# RADC-Peripherals-S06-V00.net
KiCad netlist of a schematic drawn in Altium Designer
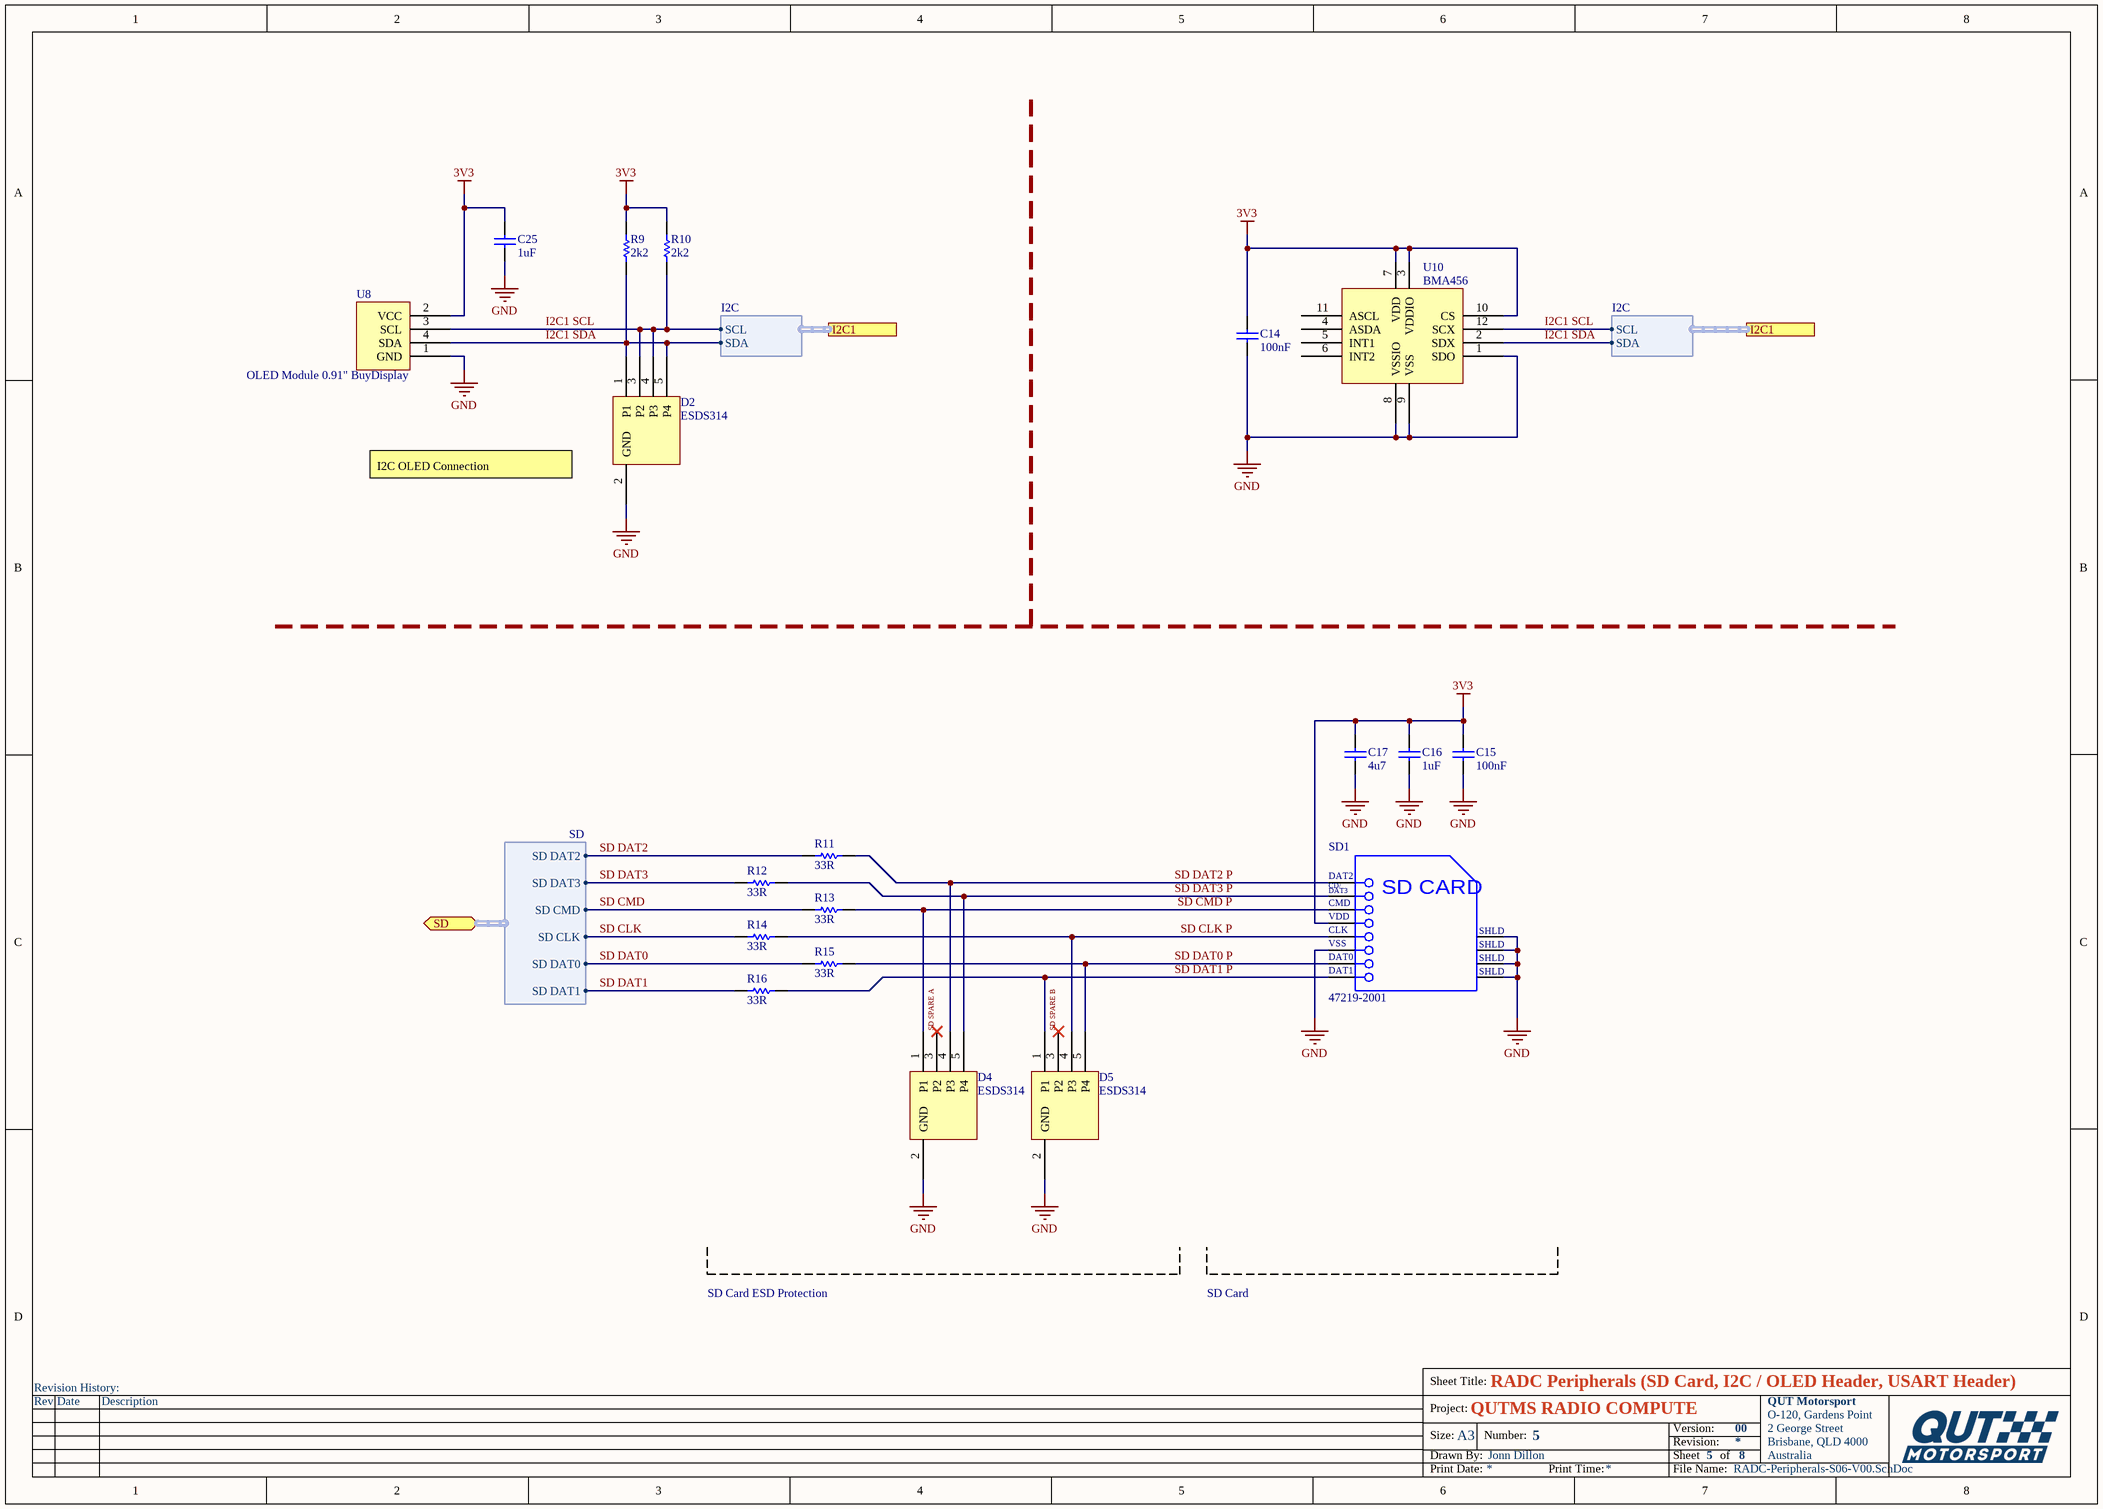
[diagram p0: RADC-Peripherals-S06-V00.SchDoc]

(export (version "E")
  (design (tool "Eeschema 10.0.6"))
  (components
    (comp (ref "C14")
      (value "100nF")
      (footprint "Cap_Ceramic_0603")
      (description "Capacitor, Ceramic, SMD, 100nF, 50V, 5%, X7R, 0603")
      (libsource (lib "StandardCapacitors") (part "100nF 50V 5% X7R 0603"))
    )
    (comp (ref "C15")
      (value "100nF")
      (footprint "Cap_Ceramic_0603")
      (description "Capacitor, Ceramic, SMD, 100nF, 50V, 5%, X7R, 0603")
      (libsource (lib "StandardCapacitors") (part "100nF 50V 5% X7R 0603"))
    )
    (comp (ref "C16")
      (value "1uF")
      (footprint "Cap_Ceramic_0603")
      (description "Capacitor, Ceramic, SMD, 1uF, 25V, 5%, X7R, 0603")
      (libsource (lib "StandardCapacitors") (part "1uF 25V 5% X7R 0603"))
    )
    (comp (ref "C17")
      (value "4u7")
      (footprint "Cap_Ceramic_0603")
      (description "Capacitor, Ceramic, SMD, 4u7, 50V, 5%, X7R, 0603")
      (libsource (lib "StandardCapacitors") (part "4u7 50V 5% X7R 0603"))
    )
    (comp (ref "C25")
      (value "1uF")
      (footprint "Cap_Ceramic_0603")
      (description "Capacitor, Ceramic, SMD, 1uF, 25V, 5%, X7R, 0603")
      (libsource (lib "StandardCapacitors") (part "1uF 25V 5% X7R 0603"))
    )
    (comp (ref "D2")
      (value "ESDS314")
      (footprint "SOT-23-5")
      (description "6.5V (Typ) Clamp 25A (8/20µs) Ipp Tvs Diode Surface Mount SOT-23-5")
      (libsource (lib "QUTMS_DiodeLibrary") (part "ESDS314"))
    )
    (comp (ref "D4")
      (value "ESDS314")
      (footprint "SOT-23-5")
      (description "6.5V (Typ) Clamp 25A (8/20µs) Ipp Tvs Diode Surface Mount SOT-23-5")
      (libsource (lib "QUTMS_DiodeLibrary") (part "ESDS314"))
    )
    (comp (ref "D5")
      (value "ESDS314")
      (footprint "SOT-23-5")
      (description "6.5V (Typ) Clamp 25A (8/20µs) Ipp Tvs Diode Surface Mount SOT-23-5")
      (libsource (lib "QUTMS_DiodeLibrary") (part "ESDS314"))
    )
    (comp (ref "R9")
      (value "2k2")
      (footprint "Res_ThinFilm_0603")
      (description "Resistor, SMD, 2k2, 0.1W, 5%, 0603")
      (libsource (lib "StandardResistors") (part "2k2 5% 0603"))
    )
    (comp (ref "R10")
      (value "2k2")
      (footprint "Res_ThinFilm_0603")
      (description "Resistor, SMD, 2k2, 0.1W, 5%, 0603")
      (libsource (lib "StandardResistors") (part "2k2 5% 0603"))
    )
    (comp (ref "R11")
      (value "33R")
      (footprint "Res_ThinFilm_0603")
      (description "Resistor, SMD, 33R, 0.1W, 5%, 0603")
      (libsource (lib "StandardResistors") (part "33R 5% 0603"))
    )
    (comp (ref "R12")
      (value "33R")
      (footprint "Res_ThinFilm_0603")
      (description "Resistor, SMD, 33R, 0.1W, 5%, 0603")
      (libsource (lib "StandardResistors") (part "33R 5% 0603"))
    )
    (comp (ref "R13")
      (value "33R")
      (footprint "Res_ThinFilm_0603")
      (description "Resistor, SMD, 33R, 0.1W, 5%, 0603")
      (libsource (lib "StandardResistors") (part "33R 5% 0603"))
    )
    (comp (ref "R14")
      (value "33R")
      (footprint "Res_ThinFilm_0603")
      (description "Resistor, SMD, 33R, 0.1W, 5%, 0603")
      (libsource (lib "StandardResistors") (part "33R 5% 0603"))
    )
    (comp (ref "R15")
      (value "33R")
      (footprint "Res_ThinFilm_0603")
      (description "Resistor, SMD, 33R, 0.1W, 5%, 0603")
      (libsource (lib "StandardResistors") (part "33R 5% 0603"))
    )
    (comp (ref "R16")
      (value "33R")
      (footprint "Res_ThinFilm_0603")
      (description "Resistor, SMD, 33R, 0.1W, 5%, 0603")
      (libsource (lib "StandardResistors") (part "33R 5% 0603"))
    )
    (comp (ref "SD1")
      (value "47219-2001")
      (footprint "47219-2001")
      (description "MicroSD Card Connector, Hinge Type, -40 to 85 degC, 8-Pin SMD, RoHS, Tape and Reel")
      (libsource (lib "QUTMS_PeripheralConnectivity") (part "47219-2001"))
    )
    (comp (ref "U8")
      (value "OLED Module 0.91\" BuyDisplay")
      (footprint "BuyDisplay 0.91\" OLED")
      (description "I2C Blue 0.91\" inch OLED Display Module 128x32 Arduino,Raspberry Pi")
      (libsource (lib "QUTMS_IntegratedCircuitLibrary") (part "OLED Module 0.91{dblquote} BuyDisplay"))
    )
    (comp (ref "U10")
      (value "BMA456")
      (footprint "BMA456")
      (description "Accelerometer X, Y, Z Axis ±2g, 4g, 8g, 16g 1.5kHz ~ 1.6kHz 12-LGA (2x2)")
      (libsource (lib "QUTMS_IntegratedCircuitLibrary") (part "BMA456"))
    )
  )
  (nets
    (net (code "3") (name "/I2C1 SCL") (class "Default")
      (node (ref "D2") (pin "3") (pinfunction "P2_3") (pintype "passive"))
      (node (ref "D2") (pin "4") (pinfunction "P3_4") (pintype "passive"))
      (node (ref "R10") (pin "1") (pinfunction "1_1") (pintype "passive"))
      (node (ref "U10") (pin "12") (pinfunction "SCX_12") (pintype "passive"))
      (node (ref "U8") (pin "3") (pinfunction "SCL_3") (pintype "passive"))
    )
    (net (code "4") (name "/I2C1 SDA") (class "Default")
      (node (ref "D2") (pin "1") (pinfunction "P1_1") (pintype "passive"))
      (node (ref "D2") (pin "5") (pinfunction "P4_5") (pintype "passive"))
      (node (ref "R9") (pin "1") (pinfunction "1_1") (pintype "passive"))
      (node (ref "U10") (pin "2") (pinfunction "SDX_2") (pintype "passive"))
      (node (ref "U8") (pin "4") (pinfunction "SDA_4") (pintype "passive"))
    )
    (net (code "5") (name "/SD CLK") (class "Default")
      (node (ref "R14") (pin "1") (pinfunction "1_1") (pintype "passive"))
    )
    (net (code "6") (name "/SD CLK P") (class "Default")
      (node (ref "D5") (pin "4") (pinfunction "P3_4") (pintype "passive"))
      (node (ref "R14") (pin "2") (pinfunction "2_2") (pintype "passive"))
      (node (ref "SD1") (pin "5") (pinfunction "CLK_5") (pintype "passive"))
    )
    (net (code "7") (name "/SD CMD") (class "Default")
      (node (ref "R13") (pin "1") (pinfunction "1_1") (pintype "passive"))
    )
    (net (code "8") (name "/SD CMD P") (class "Default")
      (node (ref "D4") (pin "1") (pinfunction "P1_1") (pintype "passive"))
      (node (ref "R13") (pin "2") (pinfunction "2_2") (pintype "passive"))
      (node (ref "SD1") (pin "3") (pinfunction "CMD_3") (pintype "passive"))
    )
    (net (code "9") (name "/SD DAT0") (class "Default")
      (node (ref "R15") (pin "1") (pinfunction "1_1") (pintype "passive"))
    )
    (net (code "10") (name "/SD DAT0 P") (class "Default")
      (node (ref "D5") (pin "5") (pinfunction "P4_5") (pintype "passive"))
      (node (ref "R15") (pin "2") (pinfunction "2_2") (pintype "passive"))
      (node (ref "SD1") (pin "7") (pinfunction "DAT0_7") (pintype "passive"))
    )
    (net (code "11") (name "/SD DAT1") (class "Default")
      (node (ref "R16") (pin "1") (pinfunction "1_1") (pintype "passive"))
    )
    (net (code "12") (name "/SD DAT1 P") (class "Default")
      (node (ref "D5") (pin "1") (pinfunction "P1_1") (pintype "passive"))
      (node (ref "R16") (pin "2") (pinfunction "2_2") (pintype "passive"))
      (node (ref "SD1") (pin "8") (pinfunction "DAT1_8") (pintype "passive"))
    )
    (net (code "13") (name "/SD DAT2") (class "Default")
      (node (ref "R11") (pin "1") (pinfunction "1_1") (pintype "passive"))
    )
    (net (code "14") (name "/SD DAT2 P") (class "Default")
      (node (ref "D4") (pin "4") (pinfunction "P3_4") (pintype "passive"))
      (node (ref "R11") (pin "2") (pinfunction "2_2") (pintype "passive"))
      (node (ref "SD1") (pin "1") (pinfunction "DAT2_1") (pintype "passive"))
    )
    (net (code "15") (name "/SD DAT3") (class "Default")
      (node (ref "R12") (pin "1") (pinfunction "1_1") (pintype "passive"))
    )
    (net (code "16") (name "/SD DAT3 P") (class "Default")
      (node (ref "D4") (pin "5") (pinfunction "P4_5") (pintype "passive"))
      (node (ref "R12") (pin "2") (pinfunction "2_2") (pintype "passive"))
      (node (ref "SD1") (pin "2") (pinfunction "CD/DAT3_2") (pintype "passive"))
    )
    (net (code "17") (name "/SD SPARE A") (class "Default")
      (node (ref "D4") (pin "3") (pinfunction "P2_3") (pintype "passive+no_connect"))
    )
    (net (code "18") (name "/SD SPARE B") (class "Default")
      (node (ref "D5") (pin "3") (pinfunction "P2_3") (pintype "passive+no_connect"))
    )
    (net (code "21") (name "3V3") (class "Default")
      (node (ref "C14") (pin "2") (pinfunction "2_2") (pintype "passive"))
      (node (ref "C15") (pin "2") (pinfunction "2_2") (pintype "passive"))
      (node (ref "C16") (pin "2") (pinfunction "2_2") (pintype "passive"))
      (node (ref "C17") (pin "2") (pinfunction "2_2") (pintype "passive"))
      (node (ref "C25") (pin "2") (pinfunction "2_2") (pintype "passive"))
      (node (ref "R10") (pin "2") (pinfunction "2_2") (pintype "passive"))
      (node (ref "R9") (pin "2") (pinfunction "2_2") (pintype "passive"))
      (node (ref "SD1") (pin "4") (pinfunction "VDD_4") (pintype "passive"))
      (node (ref "U10") (pin "10") (pinfunction "CS_10") (pintype "passive"))
      (node (ref "U10") (pin "3") (pinfunction "VDDIO_3") (pintype "passive"))
      (node (ref "U10") (pin "7") (pinfunction "VDD_7") (pintype "passive"))
      (node (ref "U8") (pin "2") (pinfunction "VCC_2") (pintype "passive"))
    )
    (net (code "22") (name "GND") (class "Default")
      (node (ref "C14") (pin "1") (pinfunction "1_1") (pintype "passive"))
      (node (ref "C15") (pin "1") (pinfunction "1_1") (pintype "passive"))
      (node (ref "C16") (pin "1") (pinfunction "1_1") (pintype "passive"))
      (node (ref "C17") (pin "1") (pinfunction "1_1") (pintype "passive"))
      (node (ref "C25") (pin "1") (pinfunction "1_1") (pintype "passive"))
      (node (ref "D2") (pin "2") (pinfunction "GND_2") (pintype "passive"))
      (node (ref "D4") (pin "2") (pinfunction "GND_2") (pintype "passive"))
      (node (ref "D5") (pin "2") (pinfunction "GND_2") (pintype "passive"))
      (node (ref "SD1") (pin "10") (pinfunction "SHLD_10") (pintype "passive"))
      (node (ref "SD1") (pin "11") (pinfunction "SHLD_11") (pintype "passive"))
      (node (ref "SD1") (pin "12") (pinfunction "SHLD_12") (pintype "passive"))
      (node (ref "SD1") (pin "6") (pinfunction "VSS_6") (pintype "passive"))
      (node (ref "SD1") (pin "9") (pinfunction "SHLD_9") (pintype "passive"))
      (node (ref "U10") (pin "1") (pinfunction "SDO_1") (pintype "passive"))
      (node (ref "U10") (pin "8") (pinfunction "VSSIO_8") (pintype "passive"))
      (node (ref "U10") (pin "9") (pinfunction "VSS_9") (pintype "passive"))
      (node (ref "U8") (pin "1") (pinfunction "GND_1") (pintype "passive"))
    )
    (net (code "23") (name "unconnected-(U10-ASCL-Pad11)") (class "Default")
      (node (ref "U10") (pin "11") (pinfunction "ASCL_11") (pintype "passive"))
    )
    (net (code "24") (name "unconnected-(U10-ASDA-Pad4)") (class "Default")
      (node (ref "U10") (pin "4") (pinfunction "ASDA_4") (pintype "passive"))
    )
    (net (code "25") (name "unconnected-(U10-INT1-Pad5)") (class "Default")
      (node (ref "U10") (pin "5") (pinfunction "INT1_5") (pintype "passive"))
    )
    (net (code "26") (name "unconnected-(U10-INT2-Pad6)") (class "Default")
      (node (ref "U10") (pin "6") (pinfunction "INT2_6") (pintype "passive"))
    )
  )
)
